# Daughter_ESCON_24-2.net
KiCad netlist of a schematic drawn in EAGLE
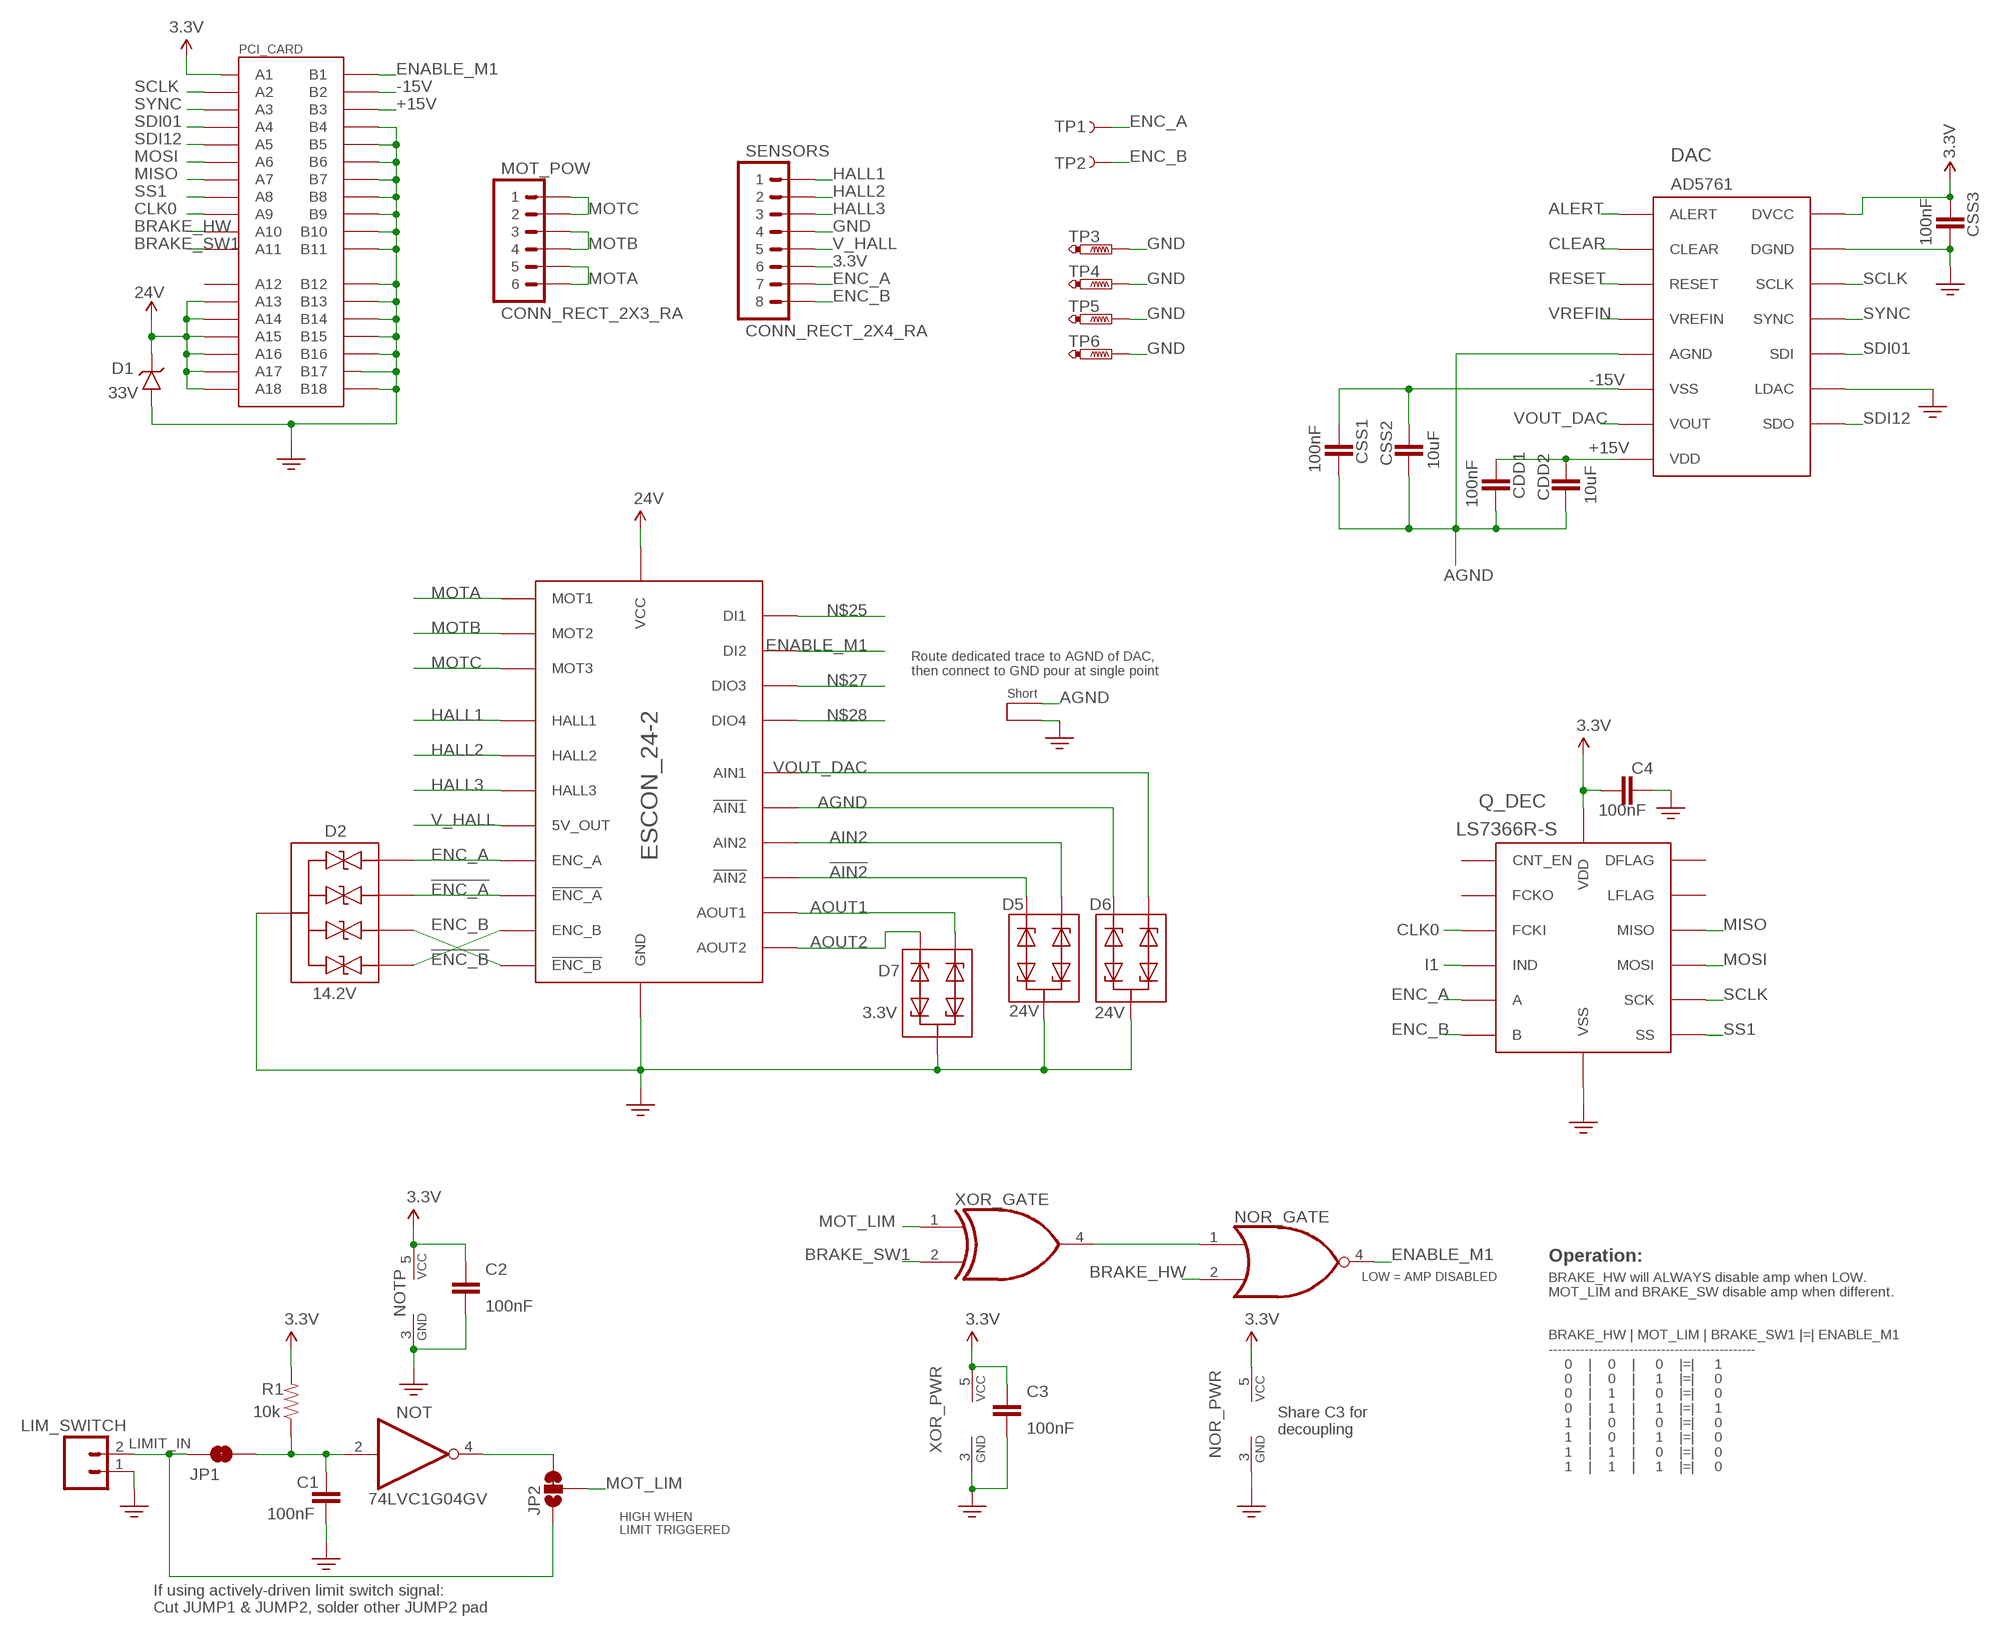
[diagram p0: schematic, sheet 1]

(export (version "E")
  (design (tool "Eeschema 10.0.6"))
  (components
    (comp (ref "C1")
      (value "100nF")
      (footprint "eagle-import:0603-CAP")
      (libsource (lib "eagle-import") (part "CAP0603-CAP"))
    )
    (comp (ref "C2")
      (value "100nF")
      (footprint "eagle-import:0603-CAP")
      (libsource (lib "eagle-import") (part "CAP0603-CAP"))
    )
    (comp (ref "C3")
      (value "100nF")
      (footprint "eagle-import:0603-CAP")
      (libsource (lib "eagle-import") (part "CAP0603-CAP"))
    )
    (comp (ref "C4")
      (value "100nF")
      (footprint "eagle-import:0603-CAP")
      (libsource (lib "eagle-import") (part "CAP0603-CAP"))
    )
    (comp (ref "CDD1")
      (value "100nF")
      (footprint "eagle-import:0603-CAP")
      (libsource (lib "eagle-import") (part "CAP0603-CAP"))
    )
    (comp (ref "CDD2")
      (value "10uF")
      (footprint "eagle-import:C0805K")
      (libsource (lib "eagle-import") (part "CAP0805"))
    )
    (comp (ref "CSS1")
      (value "100nF")
      (footprint "eagle-import:0603-CAP")
      (libsource (lib "eagle-import") (part "CAP0603-CAP"))
    )
    (comp (ref "CSS2")
      (value "10uF")
      (footprint "eagle-import:C0805K")
      (libsource (lib "eagle-import") (part "CAP0805"))
    )
    (comp (ref "CSS3")
      (value "100nF")
      (footprint "eagle-import:0603-CAP")
      (libsource (lib "eagle-import") (part "CAP0603-CAP"))
    )
    (comp (ref "D1")
      (value "33V")
      (footprint "eagle-import:DO214AA")
      (libsource (lib "eagle-import") (part "DIODE_TVS_UNIDIR_1"))
    )
    (comp (ref "D2")
      (value "14.2V")
      (footprint "eagle-import:SOTFL50P160X60-6")
      (libsource (lib "eagle-import") (part "DIODE_TVS_BIDIR_4"))
    )
    (comp (ref "D5")
      (value "24V")
      (footprint "eagle-import:SOT95P230X110-3")
      (libsource (lib "eagle-import") (part "DIODE_TVS_BIDIR_2"))
    )
    (comp (ref "D6")
      (value "24V")
      (footprint "eagle-import:SOT95P230X110-3")
      (libsource (lib "eagle-import") (part "DIODE_TVS_BIDIR_2"))
    )
    (comp (ref "D7")
      (value "3.3V")
      (footprint "eagle-import:SOT95P230X110-3")
      (libsource (lib "eagle-import") (part "DIODE_TVS_BIDIR_2"))
    )
    (comp (ref "DAC")
      (value "AD5761")
      (footprint "eagle-import:TSSOP16")
      (libsource (lib "eagle-import") (part "AD5761"))
    )
    (comp (ref "ESCON_24-2")
      (value "ESCON_MODULE24-2_BOTTOM_ENTRY")
      (footprint "eagle-import:ESCON_24-2_BOTTOM_ENTRY")
      (libsource (lib "eagle-import") (part "ESCON_MODULE24-2_BOTTOM_ENTRY"))
    )
    (comp (ref "JP1")
      (value "JUMPER-PAD-2-NC_BY_TRACE")
      (footprint "eagle-import:PAD-JUMPER-2-NC_BY_TRACE_YES_SILK")
      (libsource (lib "eagle-import") (part "JUMPER-PAD-2-NC_BY_TRACE"))
    )
    (comp (ref "JP2")
      (value "JUMPER-PAD-3-2OF3_NC_BY_TRACE")
      (footprint "eagle-import:PAD-JUMPER-3-2OF3_NC_BY_TRACE_YES_SILK_FULL_BOX")
      (libsource (lib "eagle-import") (part "JUMPER-PAD-3-2OF3_NC_BY_TRACE"))
    )
    (comp (ref "LIM_SWITCH")
      (value "22-05-7028-02")
      (footprint "eagle-import:7395-02")
      (libsource (lib "eagle-import") (part "22-?-0205-7028"))
    )
    (comp (ref "MOT_POW")
      (value "CONN_RECT_2X3_RA")
      (footprint "eagle-import:2X3-RA")
      (libsource (lib "eagle-import") (part "CONN_RECT_2X3_RA"))
    )
    (comp (ref "NOR")
      (value "NOR-SOT353")
      (footprint "eagle-import:SOT353")
      (libsource (lib "eagle-import") (part "NOR-SOT353"))
    )
    (comp (ref "NOT")
      (value "74LVC1G04GV")
      (footprint "eagle-import:SOT23-5")
      (libsource (lib "eagle-import") (part "741G04DBVLVC"))
    )
    (comp (ref "PCI_CARD")
      (value "PCIE-36-EDGE")
      (footprint "eagle-import:PCIE-36-EDGE")
      (libsource (lib "eagle-import") (part "PCIE-36-EDGE"))
    )
    (comp (ref "Q_DEC")
      (value "LS7366R-S")
      (footprint "eagle-import:SOIC-14")
      (libsource (lib "eagle-import") (part "LS7366R-S"))
    )
    (comp (ref "R1")
      (value "10k")
      (footprint "eagle-import:0603-RES")
      (libsource (lib "eagle-import") (part "RESISTOR-0603"))
    )
    (comp (ref "SENSORS")
      (value "CONN_RECT_2X4_RA")
      (footprint "eagle-import:2X4-RA")
      (libsource (lib "eagle-import") (part "CONN_RECT_2X4_RA"))
    )
    (comp (ref "TP1")
      (value "TEST-POINT_5021")
      (footprint "eagle-import:TEST-POINT_5021")
      (libsource (lib "eagle-import") (part "TEST-POINT_5021"))
    )
    (comp (ref "TP2")
      (value "TEST-POINT_5021")
      (footprint "eagle-import:TEST-POINT_5021")
      (libsource (lib "eagle-import") (part "TEST-POINT_5021"))
    )
    (comp (ref "TP3")
      (value "PTR1TP20R")
      (footprint "eagle-import:TP20R")
      (libsource (lib "eagle-import") (part "PTR1TP20R"))
    )
    (comp (ref "TP4")
      (value "PTR1TP20R")
      (footprint "eagle-import:TP20R")
      (libsource (lib "eagle-import") (part "PTR1TP20R"))
    )
    (comp (ref "TP5")
      (value "PTR1TP20R")
      (footprint "eagle-import:TP20R")
      (libsource (lib "eagle-import") (part "PTR1TP20R"))
    )
    (comp (ref "TP6")
      (value "PTR1TP20R")
      (footprint "eagle-import:TP20R")
      (libsource (lib "eagle-import") (part "PTR1TP20R"))
    )
    (comp (ref "U$1")
      (value "SHORT")
      (footprint "eagle-import:SHORT")
      (libsource (lib "eagle-import") (part "SHORT"))
    )
    (comp (ref "XOR")
      (value "XOR-SOT353")
      (footprint "eagle-import:SOT353")
      (libsource (lib "eagle-import") (part "XOR-SOT353"))
    )
  )
  (nets
    (net (code "1") (name "/+15V") (class "Default")
      (node (ref "CDD1") (pin "1") (pinfunction "1_1") (pintype "passive"))
      (node (ref "CDD2") (pin "1") (pinfunction "1_1") (pintype "passive"))
      (node (ref "DAC") (pin "8") (pinfunction "VDD_8") (pintype "power_in"))
      (node (ref "PCI_CARD") (pin "B3") (pinfunction "B3_B3") (pintype "bidirectional"))
    )
    (net (code "2") (name "/-15V") (class "Default")
      (node (ref "CSS1") (pin "1") (pinfunction "1_1") (pintype "passive"))
      (node (ref "CSS2") (pin "1") (pinfunction "1_1") (pintype "passive"))
      (node (ref "DAC") (pin "6") (pinfunction "VSS_6") (pintype "power_in"))
      (node (ref "PCI_CARD") (pin "B2") (pinfunction "B2_B2") (pintype "bidirectional"))
    )
    (net (code "3") (name "/AGND") (class "Default")
      (node (ref "CDD1") (pin "2") (pinfunction "2_2") (pintype "passive"))
      (node (ref "CDD2") (pin "2") (pinfunction "2_2") (pintype "passive"))
      (node (ref "CSS1") (pin "2") (pinfunction "2_2") (pintype "passive"))
      (node (ref "CSS2") (pin "2") (pinfunction "2_2") (pintype "passive"))
      (node (ref "D6") (pin "1") (pinfunction "2_1") (pintype "passive"))
      (node (ref "DAC") (pin "5") (pinfunction "AGND_5") (pintype "power_in"))
      (node (ref "ESCON_24-2") (pin "P$23") (pinfunction "~{AIN1}_P$23") (pintype "bidirectional"))
      (node (ref "U$1") (pin "P$1") (pinfunction "P$1_P$1") (pintype "bidirectional"))
    )
    (net (code "4") (name "/AIN2") (class "Default")
      (node (ref "D5") (pin "2") (pinfunction "1_2") (pintype "passive"))
      (node (ref "ESCON_24-2") (pin "P$22") (pinfunction "AIN2_P$22") (pintype "bidirectional"))
    )
    (net (code "5") (name "/ALERT") (class "Default")
      (node (ref "DAC") (pin "1") (pinfunction "ALERT_1") (pintype "output"))
    )
    (net (code "6") (name "/AOUT1") (class "Default")
      (node (ref "D7") (pin "2") (pinfunction "1_2") (pintype "passive"))
      (node (ref "ESCON_24-2") (pin "P$20") (pinfunction "AOUT1_P$20") (pintype "bidirectional"))
    )
    (net (code "7") (name "/AOUT2") (class "Default")
      (node (ref "D7") (pin "1") (pinfunction "2_1") (pintype "passive"))
      (node (ref "ESCON_24-2") (pin "P$19") (pinfunction "AOUT2_P$19") (pintype "bidirectional"))
    )
    (net (code "8") (name "/BRAKE_HW") (class "Default")
      (node (ref "NOR") (pin "2") (pinfunction "B_2") (pintype "input"))
      (node (ref "PCI_CARD") (pin "A10") (pinfunction "A10_A10") (pintype "bidirectional"))
    )
    (net (code "9") (name "/BRAKE_SW1") (class "Default")
      (node (ref "PCI_CARD") (pin "A11") (pinfunction "A11_A11") (pintype "bidirectional"))
      (node (ref "XOR") (pin "2") (pinfunction "B_2") (pintype "input"))
    )
    (net (code "10") (name "/CLEAR") (class "Default")
      (node (ref "DAC") (pin "2") (pinfunction "CLEAR_2") (pintype "input"))
    )
    (net (code "11") (name "/CLK0") (class "Default")
      (node (ref "PCI_CARD") (pin "A9") (pinfunction "A9_A9") (pintype "bidirectional"))
      (node (ref "Q_DEC") (pin "2") (pinfunction "FCKI_2") (pintype "bidirectional"))
    )
    (net (code "12") (name "/ENABLE_M1") (class "Default")
      (node (ref "ESCON_24-2") (pin "P$16") (pinfunction "DI2_P$16") (pintype "bidirectional"))
      (node (ref "NOR") (pin "4") (pinfunction "Y_4") (pintype "output"))
      (node (ref "PCI_CARD") (pin "B1") (pinfunction "B1_B1") (pintype "bidirectional"))
    )
    (net (code "13") (name "/ENC_A") (class "Default")
      (node (ref "D2") (pin "1") (pinfunction "IO1_1") (pintype "passive"))
      (node (ref "ESCON_24-2") (pin "P$10") (pinfunction "ENC_A_P$10") (pintype "bidirectional"))
      (node (ref "Q_DEC") (pin "12") (pinfunction "A_12") (pintype "bidirectional"))
      (node (ref "SENSORS") (pin "7") (pinfunction "7_7") (pintype "passive"))
      (node (ref "TP1") (pin "P$1") (pinfunction "1_P$1") (pintype "bidirectional"))
    )
    (net (code "14") (name "/ENC_B") (class "Default")
      (node (ref "D2") (pin "6") (pinfunction "IO4_6") (pintype "passive"))
      (node (ref "ESCON_24-2") (pin "P$12") (pinfunction "ENC_B_P$12") (pintype "bidirectional"))
      (node (ref "Q_DEC") (pin "11") (pinfunction "B_11") (pintype "bidirectional"))
      (node (ref "SENSORS") (pin "8") (pinfunction "8_8") (pintype "passive"))
      (node (ref "TP2") (pin "P$1") (pinfunction "1_P$1") (pintype "bidirectional"))
    )
    (net (code "15") (name "/HALL1") (class "Default")
      (node (ref "ESCON_24-2") (pin "P$7") (pinfunction "HALL1_P$7") (pintype "bidirectional"))
      (node (ref "SENSORS") (pin "1") (pinfunction "1_1") (pintype "passive"))
    )
    (net (code "16") (name "/HALL2") (class "Default")
      (node (ref "ESCON_24-2") (pin "P$8") (pinfunction "HALL2_P$8") (pintype "bidirectional"))
      (node (ref "SENSORS") (pin "2") (pinfunction "2_2") (pintype "passive"))
    )
    (net (code "17") (name "/HALL3") (class "Default")
      (node (ref "ESCON_24-2") (pin "P$9") (pinfunction "HALL3_P$9") (pintype "bidirectional"))
      (node (ref "SENSORS") (pin "3") (pinfunction "3_3") (pintype "passive"))
    )
    (net (code "18") (name "/I1") (class "Default")
      (node (ref "Q_DEC") (pin "10") (pinfunction "IND_10") (pintype "bidirectional"))
    )
    (net (code "19") (name "/LIMIT_IN") (class "Default")
      (node (ref "JP1") (pin "1") (pinfunction "1_1") (pintype "passive"))
      (node (ref "JP2") (pin "1") (pinfunction "1_1") (pintype "passive"))
      (node (ref "LIM_SWITCH") (pin "2") (pinfunction "2_2") (pintype "passive"))
    )
    (net (code "20") (name "/MISO") (class "Default")
      (node (ref "PCI_CARD") (pin "A7") (pinfunction "A7_A7") (pintype "bidirectional"))
      (node (ref "Q_DEC") (pin "6") (pinfunction "MISO_6") (pintype "bidirectional"))
    )
    (net (code "21") (name "/MOSI") (class "Default")
      (node (ref "PCI_CARD") (pin "A6") (pinfunction "A6_A6") (pintype "bidirectional"))
      (node (ref "Q_DEC") (pin "7") (pinfunction "MOSI_7") (pintype "bidirectional"))
    )
    (net (code "22") (name "/MOTA") (class "Default")
      (node (ref "ESCON_24-2") (pin "P$1") (pinfunction "MOT1_P$1") (pintype "bidirectional"))
      (node (ref "MOT_POW") (pin "5") (pinfunction "5_5") (pintype "passive"))
      (node (ref "MOT_POW") (pin "6") (pinfunction "6_6") (pintype "passive"))
    )
    (net (code "23") (name "/MOTB") (class "Default")
      (node (ref "ESCON_24-2") (pin "P$2") (pinfunction "MOT2_P$2") (pintype "bidirectional"))
      (node (ref "MOT_POW") (pin "3") (pinfunction "3_3") (pintype "passive"))
      (node (ref "MOT_POW") (pin "4") (pinfunction "4_4") (pintype "passive"))
    )
    (net (code "24") (name "/MOTC") (class "Default")
      (node (ref "ESCON_24-2") (pin "P$3") (pinfunction "MOT3_P$3") (pintype "bidirectional"))
      (node (ref "MOT_POW") (pin "1") (pinfunction "1_1") (pintype "passive"))
      (node (ref "MOT_POW") (pin "2") (pinfunction "2_2") (pintype "passive"))
    )
    (net (code "25") (name "/MOT_LIM") (class "Default")
      (node (ref "JP2") (pin "2") (pinfunction "2_2") (pintype "passive"))
      (node (ref "XOR") (pin "1") (pinfunction "A_1") (pintype "input"))
    )
    (net (code "26") (name "/N$25") (class "Default")
      (node (ref "ESCON_24-2") (pin "P$17") (pinfunction "DI1_P$17") (pintype "bidirectional"))
    )
    (net (code "27") (name "/N$27") (class "Default")
      (node (ref "ESCON_24-2") (pin "P$15") (pinfunction "DIO3_P$15") (pintype "bidirectional"))
    )
    (net (code "28") (name "/N$28") (class "Default")
      (node (ref "ESCON_24-2") (pin "P$14") (pinfunction "DIO4_P$14") (pintype "bidirectional"))
    )
    (net (code "29") (name "/RESET") (class "Default")
      (node (ref "DAC") (pin "3") (pinfunction "RESET_3") (pintype "input"))
    )
    (net (code "30") (name "/SCLK") (class "Default")
      (node (ref "DAC") (pin "14") (pinfunction "SCLK_14") (pintype "input"))
      (node (ref "PCI_CARD") (pin "A2") (pinfunction "A2_A2") (pintype "bidirectional"))
      (node (ref "Q_DEC") (pin "5") (pinfunction "SCK_5") (pintype "bidirectional"))
    )
    (net (code "31") (name "/SDI01") (class "Default")
      (node (ref "DAC") (pin "12") (pinfunction "SDI_12") (pintype "input"))
      (node (ref "PCI_CARD") (pin "A4") (pinfunction "A4_A4") (pintype "bidirectional"))
    )
    (net (code "32") (name "/SDI12") (class "Default")
      (node (ref "DAC") (pin "10") (pinfunction "SDO_10") (pintype "output"))
      (node (ref "PCI_CARD") (pin "A5") (pinfunction "A5_A5") (pintype "bidirectional"))
    )
    (net (code "33") (name "/SS1") (class "Default")
      (node (ref "PCI_CARD") (pin "A8") (pinfunction "A8_A8") (pintype "bidirectional"))
      (node (ref "Q_DEC") (pin "4") (pinfunction "SS_4") (pintype "bidirectional"))
    )
    (net (code "34") (name "/SYNC") (class "Default")
      (node (ref "DAC") (pin "13") (pinfunction "SYNC_13") (pintype "input"))
      (node (ref "PCI_CARD") (pin "A3") (pinfunction "A3_A3") (pintype "bidirectional"))
    )
    (net (code "35") (name "/VOUT_DAC") (class "Default")
      (node (ref "D6") (pin "2") (pinfunction "1_2") (pintype "passive"))
      (node (ref "DAC") (pin "7") (pinfunction "VOUT_7") (pintype "power_in"))
      (node (ref "ESCON_24-2") (pin "P$24") (pinfunction "AIN1_P$24") (pintype "bidirectional"))
    )
    (net (code "36") (name "/VREFIN") (class "Default")
      (node (ref "DAC") (pin "4") (pinfunction "VREFIN_4") (pintype "bidirectional"))
    )
    (net (code "37") (name "/V_HALL") (class "Default")
      (node (ref "ESCON_24-2") (pin "P$6") (pinfunction "5V_OUT_P$6") (pintype "bidirectional"))
      (node (ref "SENSORS") (pin "5") (pinfunction "5_5") (pintype "passive"))
    )
    (net (code "38") (name "/~{AIN2}") (class "Default")
      (node (ref "D5") (pin "1") (pinfunction "2_1") (pintype "passive"))
      (node (ref "ESCON_24-2") (pin "P$21") (pinfunction "~{AIN2}_P$21") (pintype "bidirectional"))
    )
    (net (code "39") (name "/~{ENC_A}") (class "Default")
      (node (ref "D2") (pin "3") (pinfunction "IO2_3") (pintype "passive"))
      (node (ref "ESCON_24-2") (pin "P$11") (pinfunction "~{ENC_A}_P$11") (pintype "bidirectional"))
    )
    (net (code "40") (name "/~{ENC_B}") (class "Default")
      (node (ref "D2") (pin "4") (pinfunction "IO3_4") (pintype "passive"))
      (node (ref "ESCON_24-2") (pin "P$13") (pinfunction "~{ENC_B}_P$13") (pintype "bidirectional"))
    )
    (net (code "41") (name "3.3V") (class "Default")
      (node (ref "C2") (pin "1") (pinfunction "1_1") (pintype "passive"))
      (node (ref "C3") (pin "1") (pinfunction "1_1") (pintype "passive"))
      (node (ref "C4") (pin "1") (pinfunction "1_1") (pintype "passive"))
      (node (ref "CSS3") (pin "1") (pinfunction "1_1") (pintype "passive"))
      (node (ref "DAC") (pin "15") (pinfunction "DVCC_15") (pintype "power_in"))
      (node (ref "NOR") (pin "5") (pinfunction "VCC_5") (pintype "power_in"))
      (node (ref "NOT") (pin "5") (pinfunction "VCC_5") (pintype "power_in"))
      (node (ref "PCI_CARD") (pin "A1") (pinfunction "A1_A1") (pintype "bidirectional"))
      (node (ref "Q_DEC") (pin "14") (pinfunction "VDD_14") (pintype "bidirectional"))
      (node (ref "R1") (pin "2") (pinfunction "2_2") (pintype "passive"))
      (node (ref "SENSORS") (pin "6") (pinfunction "6_6") (pintype "passive"))
      (node (ref "XOR") (pin "5") (pinfunction "VCC_5") (pintype "power_in"))
    )
    (net (code "42") (name "24V") (class "Default")
      (node (ref "D1") (pin "C") (pinfunction "C_C") (pintype "passive"))
      (node (ref "ESCON_24-2") (pin "P$4") (pinfunction "VCC_P$4") (pintype "bidirectional"))
      (node (ref "PCI_CARD") (pin "A13") (pinfunction "A13_A13") (pintype "bidirectional"))
      (node (ref "PCI_CARD") (pin "A14") (pinfunction "A14_A14") (pintype "bidirectional"))
      (node (ref "PCI_CARD") (pin "A15") (pinfunction "A15_A15") (pintype "bidirectional"))
      (node (ref "PCI_CARD") (pin "A16") (pinfunction "A16_A16") (pintype "bidirectional"))
      (node (ref "PCI_CARD") (pin "A17") (pinfunction "A17_A17") (pintype "bidirectional"))
      (node (ref "PCI_CARD") (pin "A18") (pinfunction "A18_A18") (pintype "bidirectional"))
    )
    (net (code "43") (name "GND2") (class "Default")
      (node (ref "C1") (pin "2") (pinfunction "2_2") (pintype "passive"))
      (node (ref "C2") (pin "2") (pinfunction "2_2") (pintype "passive"))
      (node (ref "C3") (pin "2") (pinfunction "2_2") (pintype "passive"))
      (node (ref "C4") (pin "2") (pinfunction "2_2") (pintype "passive"))
      (node (ref "CSS3") (pin "2") (pinfunction "2_2") (pintype "passive"))
      (node (ref "D1") (pin "A") (pinfunction "A_A") (pintype "passive"))
      (node (ref "D2") (pin "2") (pinfunction "GND_2") (pintype "passive"))
      (node (ref "D2") (pin "5") (pinfunction "GND_5") (pintype "passive"))
      (node (ref "D5") (pin "3") (pinfunction "3_3") (pintype "passive"))
      (node (ref "D6") (pin "3") (pinfunction "3_3") (pintype "passive"))
      (node (ref "D7") (pin "3") (pinfunction "3_3") (pintype "passive"))
      (node (ref "DAC") (pin "11") (pinfunction "LDAC_11") (pintype "input"))
      (node (ref "DAC") (pin "16") (pinfunction "DGND_16") (pintype "power_in"))
      (node (ref "ESCON_24-2") (pin "P$18") (pinfunction "GND_P$18") (pintype "bidirectional"))
      (node (ref "ESCON_24-2") (pin "P$5") (pinfunction "GND_P$5") (pintype "bidirectional"))
      (node (ref "LIM_SWITCH") (pin "1") (pinfunction "1_1") (pintype "passive"))
      (node (ref "NOR") (pin "3") (pinfunction "GND_3") (pintype "power_in"))
      (node (ref "NOT") (pin "3") (pinfunction "GND_3") (pintype "power_in"))
      (node (ref "PCI_CARD") (pin "B10") (pinfunction "B10_B10") (pintype "bidirectional"))
      (node (ref "PCI_CARD") (pin "B11") (pinfunction "B11_B11") (pintype "bidirectional"))
      (node (ref "PCI_CARD") (pin "B12") (pinfunction "B12_B12") (pintype "bidirectional"))
      (node (ref "PCI_CARD") (pin "B13") (pinfunction "B13_B13") (pintype "bidirectional"))
      (node (ref "PCI_CARD") (pin "B14") (pinfunction "B14_B14") (pintype "bidirectional"))
      (node (ref "PCI_CARD") (pin "B15") (pinfunction "B15_B15") (pintype "bidirectional"))
      (node (ref "PCI_CARD") (pin "B16") (pinfunction "B16_B16") (pintype "bidirectional"))
      (node (ref "PCI_CARD") (pin "B17") (pinfunction "B17_B17") (pintype "bidirectional"))
      (node (ref "PCI_CARD") (pin "B18") (pinfunction "B18_B18") (pintype "bidirectional"))
      (node (ref "PCI_CARD") (pin "B4") (pinfunction "B4_B4") (pintype "bidirectional"))
      (node (ref "PCI_CARD") (pin "B5") (pinfunction "B5_B5") (pintype "bidirectional"))
      (node (ref "PCI_CARD") (pin "B6") (pinfunction "B6_B6") (pintype "bidirectional"))
      (node (ref "PCI_CARD") (pin "B7") (pinfunction "B7_B7") (pintype "bidirectional"))
      (node (ref "PCI_CARD") (pin "B8") (pinfunction "B8_B8") (pintype "bidirectional"))
      (node (ref "PCI_CARD") (pin "B9") (pinfunction "B9_B9") (pintype "bidirectional"))
      (node (ref "Q_DEC") (pin "3") (pinfunction "VSS_3") (pintype "bidirectional"))
      (node (ref "SENSORS") (pin "4") (pinfunction "4_4") (pintype "passive"))
      (node (ref "TP3") (pin "TP") (pinfunction "TP_TP") (pintype "input"))
      (node (ref "TP4") (pin "TP") (pinfunction "TP_TP") (pintype "input"))
      (node (ref "TP5") (pin "TP") (pinfunction "TP_TP") (pintype "input"))
      (node (ref "TP6") (pin "TP") (pinfunction "TP_TP") (pintype "input"))
      (node (ref "U$1") (pin "P$2") (pinfunction "P$2_P$2") (pintype "bidirectional"))
      (node (ref "XOR") (pin "3") (pinfunction "GND_3") (pintype "power_in"))
    )
    (net (code "44") (name "Net-(NORA-A)") (class "Default")
      (node (ref "NOR") (pin "1") (pinfunction "A_1") (pintype "input"))
      (node (ref "XOR") (pin "4") (pinfunction "Y_4") (pintype "output"))
    )
    (net (code "45") (name "Net-(NOTA-I)") (class "Default")
      (node (ref "C1") (pin "1") (pinfunction "1_1") (pintype "passive"))
      (node (ref "JP1") (pin "2") (pinfunction "2_2") (pintype "passive"))
      (node (ref "NOT") (pin "2") (pinfunction "I_2") (pintype "input"))
      (node (ref "R1") (pin "1") (pinfunction "1_1") (pintype "passive"))
    )
    (net (code "46") (name "Net-(NOTA-O)") (class "Default")
      (node (ref "JP2") (pin "3") (pinfunction "3_3") (pintype "passive"))
      (node (ref "NOT") (pin "4") (pinfunction "O_4") (pintype "output"))
    )
    (net (code "47") (name "unconnected-(PCI_CARD-PadA12)") (class "Default")
      (node (ref "PCI_CARD") (pin "A12") (pinfunction "A12_A12") (pintype "bidirectional"))
    )
    (net (code "48") (name "unconnected-(Q_DEC-CNT_EN-Pad13)") (class "Default")
      (node (ref "Q_DEC") (pin "13") (pinfunction "CNT_EN_13") (pintype "bidirectional"))
    )
    (net (code "49") (name "unconnected-(Q_DEC-DFLAG-Pad9)") (class "Default")
      (node (ref "Q_DEC") (pin "9") (pinfunction "DFLAG_9") (pintype "bidirectional"))
    )
    (net (code "50") (name "unconnected-(Q_DEC-FCKO-Pad1)") (class "Default")
      (node (ref "Q_DEC") (pin "1") (pinfunction "FCKO_1") (pintype "bidirectional"))
    )
    (net (code "51") (name "unconnected-(Q_DEC-LFLAG-Pad8)") (class "Default")
      (node (ref "Q_DEC") (pin "8") (pinfunction "LFLAG_8") (pintype "bidirectional"))
    )
  )
)
